# SAMC21N_Xplained_Pro_EDBG.net
KiCad netlist of a schematic drawn in Altium Designer
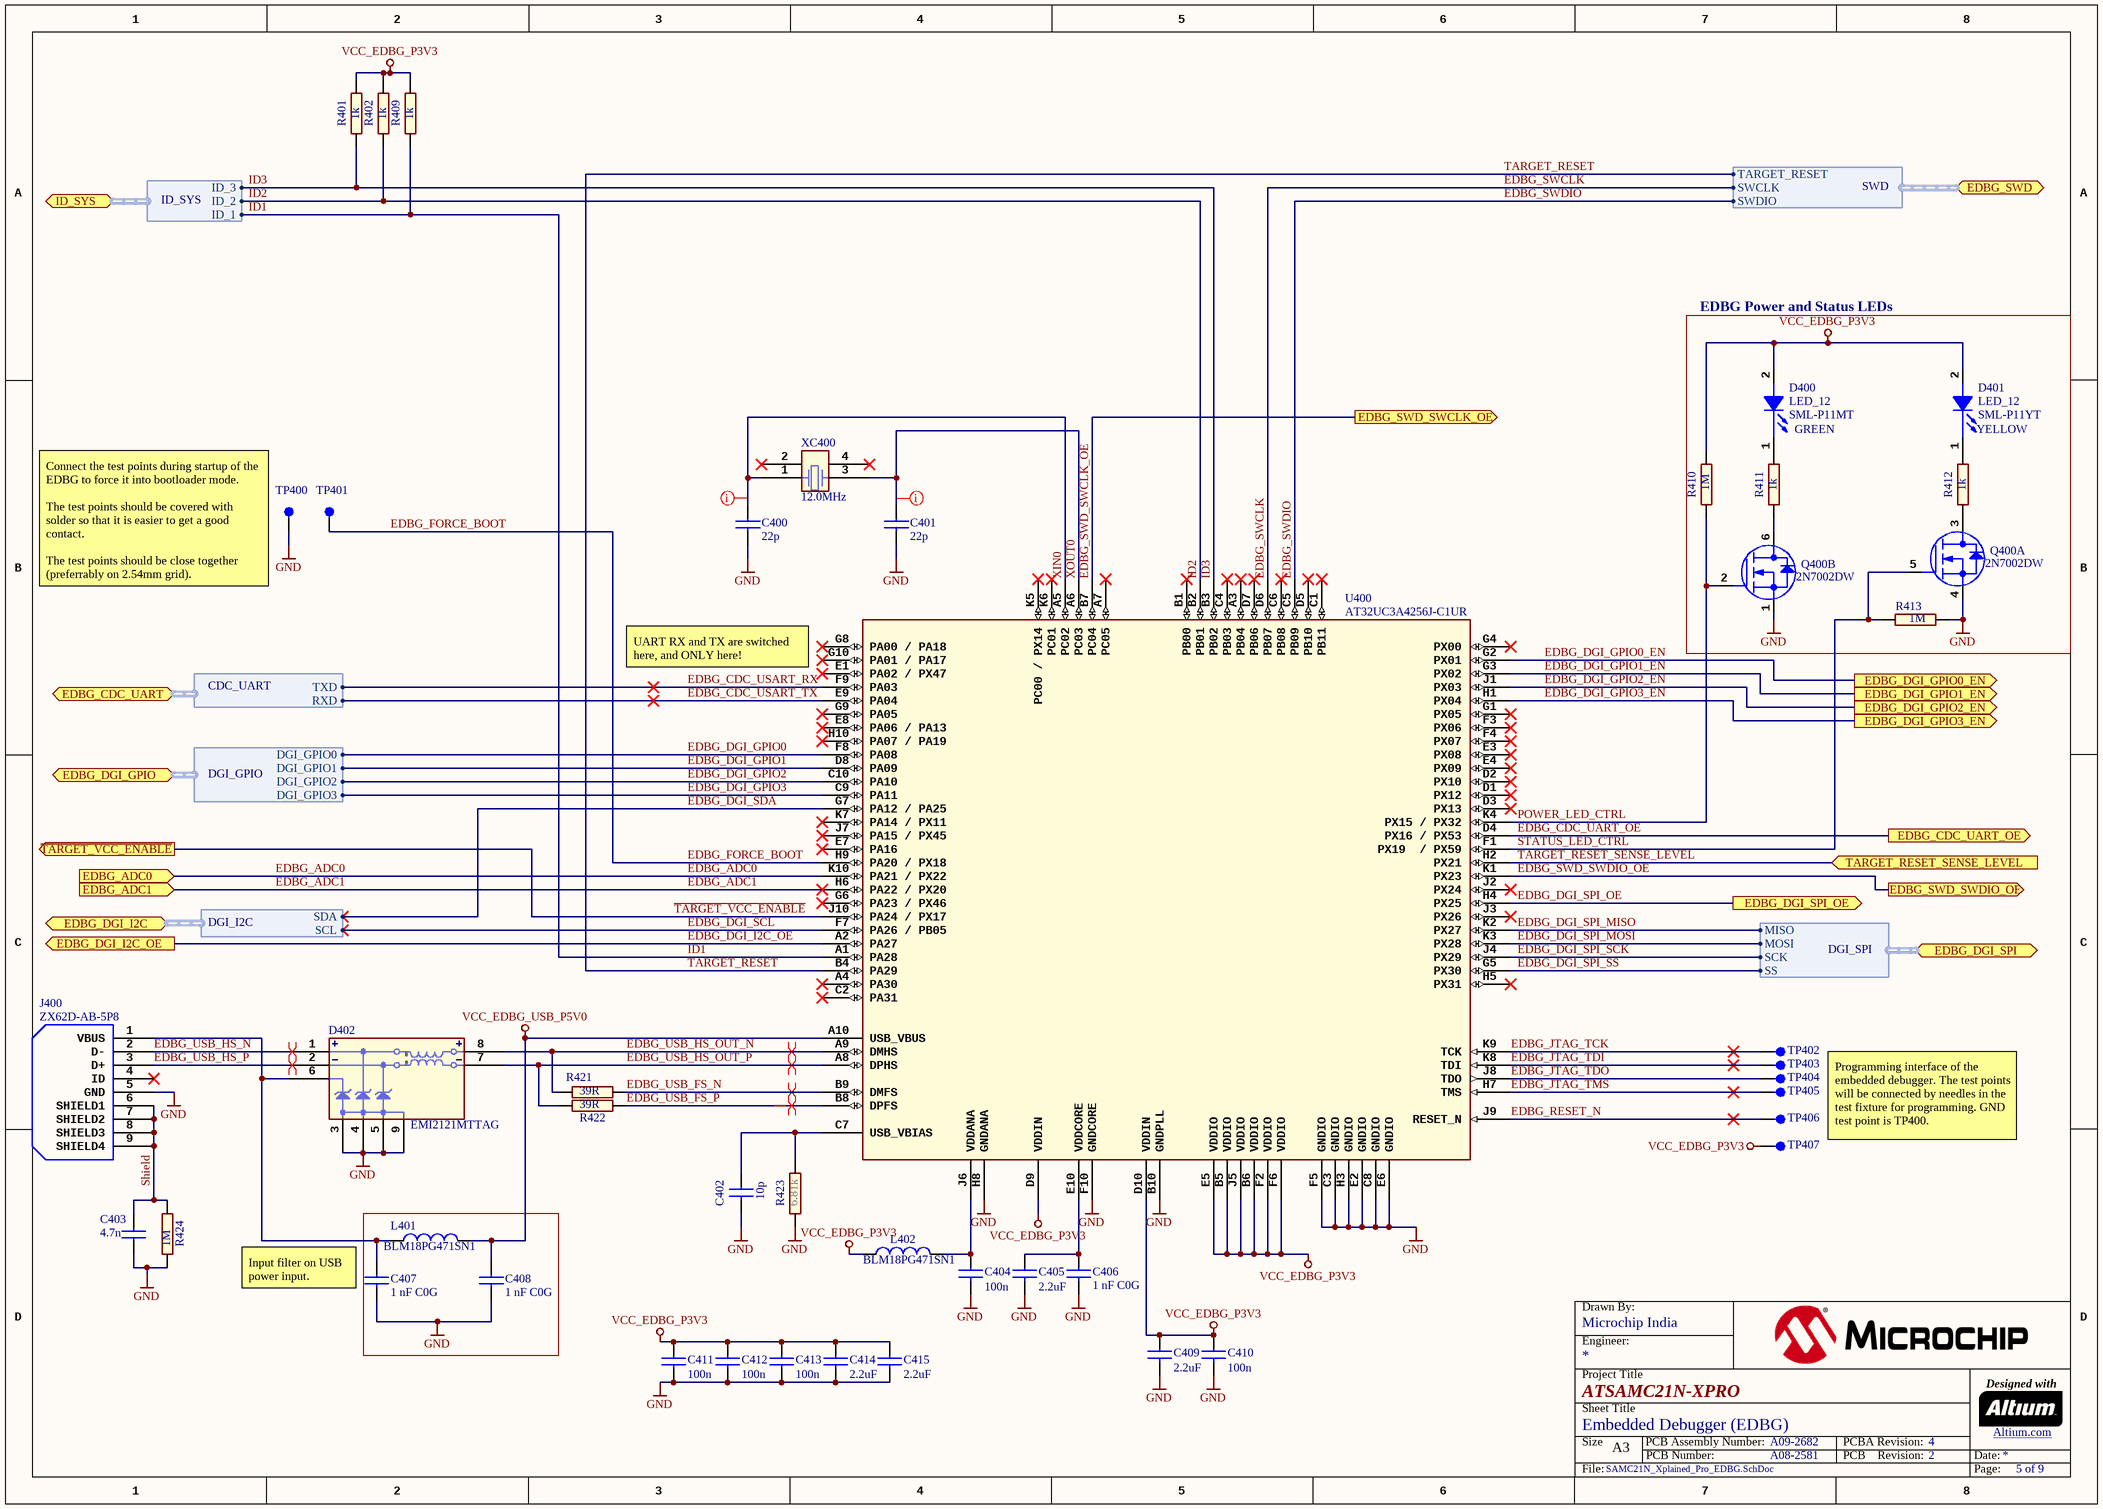
[diagram p0: SAMC21N_Xplained_Pro_EDBG.SchDoc]

(export (version "E")
  (design (tool "Eeschema 10.0.6"))
  (components
    (comp (ref "C400")
      (value "22p")
      (footprint "AP1-00053")
      (description "Ceramic capacitor, SMD 0402, NP0, 50V, +/-5%")
      (fields (field (name "TOLERANCE") "50V, +/-5%") (field (name "VERIFIED BY") "Lars Helge Mo"))
      (libsource (lib "AltiumDbLib") (part "CAP-NONPOL"))
    )
    (comp (ref "C401")
      (value "22p")
      (footprint "AP1-00053")
      (description "Ceramic capacitor, SMD 0402, NP0, 50V, +/-5%")
      (fields (field (name "TOLERANCE") "50V, +/-5%") (field (name "VERIFIED BY") "Lars Helge Mo"))
      (libsource (lib "AltiumDbLib") (part "CAP-NONPOL"))
    )
    (comp (ref "C402")
      (value "10p")
      (footprint "AP1-00053")
      (description "Ceramic capacitor, SMD 0402, NP0, 50V, +/-5%")
      (fields (field (name "TOLERANCE") "50V, +/-5%") (field (name "VERIFIED BY") "Lars Helge Mo"))
      (libsource (lib "AltiumDbLib") (part "CAP-NONPOL"))
    )
    (comp (ref "C403")
      (value "4.7n")
      (footprint "AP1-00053")
      (description "Ceramic capacitor, SMD 0402, X7R, 25V, +/-10%")
      (fields
        (field (name "TOLERANCE") "25V, +/-10%")
        (field (name "Comment") "CAP-NONPOL")
        (field (name "VERIFIED BY") "Lars Helge Mo")
      )
      (libsource (lib "AltiumDbLib") (part "CAP-NONPOL"))
    )
    (comp (ref "C404")
      (value "100n")
      (footprint "AP1-00053")
      (description "Ceramic capacitor, SMD 0402, X7R, 16V, +/-10%")
      (fields
        (field (name "TOLERANCE") "16V, +/-10%")
        (field (name "MANUFACTURER") "Kemet")
        (field (name "VERIFIED BY") "Lars Helge Mo")
      )
      (libsource (lib "AltiumDbLib") (part "CAP-NONPOL"))
    )
    (comp (ref "C405")
      (value "2.2uF")
      (footprint "AP1-00053")
      (description "Ceramic capacitor, SMD 0402, X5R, 6.3V, +/-20%")
      (fields
        (field (name "TOLERANCE") "±20%")
        (field (name "MANUFACTURER") "Kemet")
        (field (name "VERIFIED BY") "Lars Helge Mo")
      )
      (libsource (lib "AltiumDbLib") (part "CAP-NONPOL"))
    )
    (comp (ref "C406")
      (value "1 nF C0G")
      (footprint "AP1-00053")
      (description "Ceramic capacitor, SMD 0402, C0G, 50V, +/-5%")
      (fields
        (field (name "TOLERANCE") "5%")
        (field (name "MANUFACTURER") "Murata")
        (field (name "VERIFIED BY") "Lars Helge Mo")
      )
      (libsource (lib "AltiumDbLib") (part "CAP-NONPOL"))
    )
    (comp (ref "C407")
      (value "1 nF C0G")
      (footprint "AP1-00053")
      (description "Ceramic capacitor, SMD 0402, C0G, 50V, +/-5%")
      (fields
        (field (name "TOLERANCE") "5%")
        (field (name "MANUFACTURER") "Murata")
        (field (name "VERIFIED BY") "Lars Helge Mo")
      )
      (libsource (lib "AltiumDbLib") (part "CAP-NONPOL"))
    )
    (comp (ref "C408")
      (value "1 nF C0G")
      (footprint "AP1-00053")
      (description "Ceramic capacitor, SMD 0402, C0G, 50V, +/-5%")
      (fields
        (field (name "TOLERANCE") "5%")
        (field (name "MANUFACTURER") "Murata")
        (field (name "VERIFIED BY") "Lars Helge Mo")
      )
      (libsource (lib "AltiumDbLib") (part "CAP-NONPOL"))
    )
    (comp (ref "C409")
      (value "2.2uF")
      (footprint "AP1-00053")
      (description "Ceramic capacitor, SMD 0402, X5R, 6.3V, +/-20%")
      (fields
        (field (name "TOLERANCE") "±20%")
        (field (name "MANUFACTURER") "Kemet")
        (field (name "VERIFIED BY") "Lars Helge Mo")
      )
      (libsource (lib "AltiumDbLib") (part "CAP-NONPOL"))
    )
    (comp (ref "C410")
      (value "100n")
      (footprint "AP1-00053")
      (description "Ceramic capacitor, SMD 0402, X7R, 16V, +/-10%")
      (fields
        (field (name "TOLERANCE") "16V, +/-10%")
        (field (name "MANUFACTURER") "Kemet")
        (field (name "VERIFIED BY") "Lars Helge Mo")
      )
      (libsource (lib "AltiumDbLib") (part "CAP-NONPOL"))
    )
    (comp (ref "C411")
      (value "100n")
      (footprint "AP1-00053")
      (description "Ceramic capacitor, SMD 0402, X7R, 16V, +/-10%")
      (fields
        (field (name "TOLERANCE") "16V, +/-10%")
        (field (name "MANUFACTURER") "Kemet")
        (field (name "VERIFIED BY") "Lars Helge Mo")
      )
      (libsource (lib "AltiumDbLib") (part "CAP-NONPOL"))
    )
    (comp (ref "C412")
      (value "100n")
      (footprint "AP1-00053")
      (description "Ceramic capacitor, SMD 0402, X7R, 16V, +/-10%")
      (fields
        (field (name "TOLERANCE") "16V, +/-10%")
        (field (name "MANUFACTURER") "Kemet")
        (field (name "VERIFIED BY") "Lars Helge Mo")
      )
      (libsource (lib "AltiumDbLib") (part "CAP-NONPOL"))
    )
    (comp (ref "C413")
      (value "100n")
      (footprint "AP1-00053")
      (description "Ceramic capacitor, SMD 0402, X7R, 16V, +/-10%")
      (fields
        (field (name "TOLERANCE") "16V, +/-10%")
        (field (name "MANUFACTURER") "Kemet")
        (field (name "VERIFIED BY") "Lars Helge Mo")
      )
      (libsource (lib "AltiumDbLib") (part "CAP-NONPOL"))
    )
    (comp (ref "C414")
      (value "2.2uF")
      (footprint "AP1-00053")
      (description "Ceramic capacitor, SMD 0402, X5R, 6.3V, +/-20%")
      (fields
        (field (name "TOLERANCE") "±20%")
        (field (name "MANUFACTURER") "Kemet")
        (field (name "VERIFIED BY") "Lars Helge Mo")
      )
      (libsource (lib "AltiumDbLib") (part "CAP-NONPOL"))
    )
    (comp (ref "C415")
      (value "2.2uF")
      (footprint "AP1-00053")
      (description "Ceramic capacitor, SMD 0402, X5R, 6.3V, +/-20%")
      (fields
        (field (name "TOLERANCE") "±20%")
        (field (name "MANUFACTURER") "Kemet")
        (field (name "VERIFIED BY") "Lars Helge Mo")
      )
      (libsource (lib "AltiumDbLib") (part "CAP-NONPOL"))
    )
    (comp (ref "D400")
      (value "LED_12")
      (footprint "AP4-00160")
      (description "LED, SMD 0402, Green, Wave length=569nm, 2.1mcd @ (1mA, 1.9Vf)")
      (fields
        (field (name "ALTIUM_VALUE") "SML-P11MT")
        (field (name "MANUFACTURER") "ROHM")
        (field (name "MPN") "SML-P11MT-T86")
        (field (name "VERIFIED BY") "Sveinung Helgeland")
      )
      (libsource (lib "AltiumDbLib") (part "LED_12"))
    )
    (comp (ref "D401")
      (value "LED_12")
      (footprint "AP4-00160")
      (description "LED, SMD 0402, Yellow, Wave length=586nm, 7.6mcd @ (1mA, 1.9Vf)")
      (fields
        (field (name "ALTIUM_VALUE") "SML-P11YT")
        (field (name "MANUFACTURER") "ROHM")
        (field (name "MPN") "SML-P11YT-T86")
        (field (name "VERIFIED BY") "Sveinung Helgeland")
      )
      (libsource (lib "AltiumDbLib") (part "LED_12"))
    )
    (comp (ref "D402")
      (value "EMI2121MTTAG")
      (footprint "AP4-00159")
      (description "EMI2121, SZEMI2121 Single Pair Common Mode Filter with ESD Protection")
      (fields (field (name "MANUFACTURER") "ON Semiconductor") (field (name "Comment") "WDFN8"))
      (libsource (lib "AltiumDbLib") (part "EMI2121"))
    )
    (comp (ref "J400")
      (value "ZX62D-AB-5P8")
      (footprint "AP8-00852")
      (description "Micro USB AB Connector, Standard SMT + DIP")
      (fields (field (name "Comment") "2,000 pieces per reel") (field (name "VERIFIED BY") "Eirik Rasmussen"))
      (libsource (lib "AltiumDbLib") (part "USB_AB"))
    )
    (comp (ref "L401")
      (value "BLM18PG471SN1")
      (footprint "AP3-00005")
      (description "SMD RF inductor 0603. Z=470Ohm (@100MHz), Max R(dc)=0.65Ohm, Max current=1A")
      (fields
        (field (name "TOLERANCE") "±25%")
        (field (name "MANUFACTURER") "Murata")
        (field (name "VERIFIED BY") "Lars Helge Mo")
      )
      (libsource (lib "AltiumDbLib") (part "INDUCTOR"))
    )
    (comp (ref "L402")
      (value "BLM18PG471SN1")
      (footprint "AP3-00005")
      (description "SMD RF inductor 0603. Z=470Ohm (@100MHz), Max R(dc)=0.65Ohm, Max current=1A")
      (fields
        (field (name "TOLERANCE") "±25%")
        (field (name "MANUFACTURER") "Murata")
        (field (name "VERIFIED BY") "Lars Helge Mo")
      )
      (libsource (lib "AltiumDbLib") (part "INDUCTOR"))
    )
    (comp (ref "Q400")
      (value "2N7002DW")
      (footprint "AP5-00001")
      (description "Dual N-Channel MOSFET, 60V, 115mA cont,RDS(ON) < 7.5 Ohm @50mA@5V, SOT-363")
      (fields
        (field (name "MANUFACTURER") "Fairchild")
        (field (name "Comment") "Same as 2N7002 but with two MOSFETs in one package")
      )
      (libsource (lib "AltiumDbLib") (part "MOSFET_DUAL_N_S2G2D1S1G1D2"))
    )
    (comp (ref "R401")
      (value "1k")
      (footprint "AP2-00000")
      (description "Thick film resistor, SMD 0402, 1/16W, 1%")
      (fields
        (field (name "TOLERANCE") "1 %")
        (field (name "Comment") "R2")
        (field (name "VERIFIED BY") "Lars Helge Mo")
      )
      (libsource (lib "AltiumDbLib") (part "R2"))
    )
    (comp (ref "R402")
      (value "1k")
      (footprint "AP2-00000")
      (description "Thick film resistor, SMD 0402, 1/16W, 1%")
      (fields
        (field (name "TOLERANCE") "1 %")
        (field (name "Comment") "R2")
        (field (name "VERIFIED BY") "Lars Helge Mo")
      )
      (libsource (lib "AltiumDbLib") (part "R2"))
    )
    (comp (ref "R409")
      (value "1k")
      (footprint "AP2-00000")
      (description "Thick film resistor, SMD 0402, 1/16W, 1%")
      (fields
        (field (name "TOLERANCE") "1 %")
        (field (name "Comment") "R2")
        (field (name "VERIFIED BY") "Lars Helge Mo")
      )
      (libsource (lib "AltiumDbLib") (part "R2"))
    )
    (comp (ref "R410")
      (value "1M")
      (footprint "AP2-00000")
      (description "Thick film resistor, SMD 0402, 1/16W, 1%")
      (fields
        (field (name "TOLERANCE") "1 %")
        (field (name "MANUFACTURER") "KOA")
        (field (name "VERIFIED BY") "Lars Helge Mo")
      )
      (libsource (lib "AltiumDbLib") (part "R2"))
    )
    (comp (ref "R411")
      (value "1k")
      (footprint "AP2-00000")
      (description "Thick film resistor, SMD 0402, 1/16W, 1%")
      (fields
        (field (name "TOLERANCE") "1 %")
        (field (name "MANUFACTURER") "ASJ")
        (field (name "VERIFIED BY") "Lars Helge Mo")
      )
      (libsource (lib "AltiumDbLib") (part "R2"))
    )
    (comp (ref "R412")
      (value "1k")
      (footprint "AP2-00000")
      (description "Thick film resistor, SMD 0402, 1/16W, 1%")
      (fields
        (field (name "TOLERANCE") "1 %")
        (field (name "MANUFACTURER") "ASJ")
        (field (name "VERIFIED BY") "Lars Helge Mo")
      )
      (libsource (lib "AltiumDbLib") (part "R2"))
    )
    (comp (ref "R413")
      (value "1M")
      (footprint "AP2-00000")
      (description "Thick film resistor, SMD 0402, 1/16W, 1%")
      (fields
        (field (name "TOLERANCE") "1 %")
        (field (name "MANUFACTURER") "KOA")
        (field (name "VERIFIED BY") "Lars Helge Mo")
      )
      (libsource (lib "") (part "R2_2"))
    )
    (comp (ref "R421")
      (value "39R")
      (footprint "AP2-00011")
      (description "Thick film resistor, SMD 0402, 1/16W, 1%")
      (fields
        (field (name "TOLERANCE") "1 %")
        (field (name "Comment") "R2")
        (field (name "VERIFIED BY") "Lars Helge Mo")
      )
      (libsource (lib "") (part "R2_1"))
    )
    (comp (ref "R422")
      (value "39R")
      (footprint "AP2-00011")
      (description "Thick film resistor, SMD 0402, 1/16W, 1%")
      (fields
        (field (name "TOLERANCE") "1 %")
        (field (name "Comment") "R2")
        (field (name "VERIFIED BY") "Lars Helge Mo")
      )
      (libsource (lib "") (part "R2_1"))
    )
    (comp (ref "R423")
      (value "6.81k")
      (footprint "AP2-00011")
      (description "Thick film resistor, SMD 0402, 1/16W, 1%")
      (fields
        (field (name "TOLERANCE") "1%")
        (field (name "Comment") "R2")
        (field (name "VERIFIED BY") "Lars Helge Mo")
      )
      (libsource (lib "AltiumDbLib") (part "R2"))
    )
    (comp (ref "R424")
      (value "1M")
      (footprint "AP2-00011")
      (description "Thick film resistor, SMD 0402, 1/16W, 1%")
      (fields
        (field (name "TOLERANCE") "1 %")
        (field (name "MANUFACTURER") "KOA")
        (field (name "VERIFIED BY") "Lars Helge Mo")
      )
      (libsource (lib "") (part "R2_3"))
    )
    (comp (ref "TP400")
      (value "TESTPAD")
      (footprint "AP8-00010")
      (description "Single SMD testpad")
      (fields (field (name "VERIFIED BY") "Sveinung Helgeland"))
      (libsource (lib "AltiumDbLib") (part "TESTPOINT"))
    )
    (comp (ref "TP401")
      (value "TESTPAD")
      (footprint "AP8-00010")
      (description "Single SMD testpad")
      (fields (field (name "VERIFIED BY") "Sveinung Helgeland"))
      (libsource (lib "AltiumDbLib") (part "TESTPOINT"))
    )
    (comp (ref "TP402")
      (value "TESTPAD")
      (footprint "AP8-00010")
      (description "Single SMD testpad")
      (fields (field (name "VERIFIED BY") "Sveinung Helgeland"))
      (libsource (lib "AltiumDbLib") (part "TESTPOINT"))
    )
    (comp (ref "TP403")
      (value "TESTPAD")
      (footprint "AP8-00010")
      (description "Single SMD testpad")
      (fields (field (name "VERIFIED BY") "Sveinung Helgeland"))
      (libsource (lib "AltiumDbLib") (part "TESTPOINT"))
    )
    (comp (ref "TP404")
      (value "TESTPAD")
      (footprint "AP8-00010")
      (description "Single SMD testpad")
      (fields (field (name "VERIFIED BY") "Sveinung Helgeland"))
      (libsource (lib "AltiumDbLib") (part "TESTPOINT"))
    )
    (comp (ref "TP405")
      (value "TESTPAD")
      (footprint "AP8-00010")
      (description "Single SMD testpad")
      (fields (field (name "VERIFIED BY") "Sveinung Helgeland"))
      (libsource (lib "AltiumDbLib") (part "TESTPOINT"))
    )
    (comp (ref "TP406")
      (value "TESTPAD")
      (footprint "AP8-00010")
      (description "Single SMD testpad")
      (fields (field (name "VERIFIED BY") "Sveinung Helgeland"))
      (libsource (lib "AltiumDbLib") (part "TESTPOINT"))
    )
    (comp (ref "TP407")
      (value "TESTPAD")
      (footprint "AP8-00010")
      (description "Single SMD testpad")
      (fields (field (name "VERIFIED BY") "Sveinung Helgeland"))
      (libsource (lib "AltiumDbLib") (part "TESTPOINT"))
    )
    (comp (ref "U400")
      (value "AT32UC3A4256J-C1UR")
      (footprint "AP6-00206")
      (description "AVR 32-bit RISC MCU")
      (fields (field (name "MANUFACTURER") "ATMEL") (field (name "Comment") "100 ball VFBGA"))
      (libsource (lib "AltiumDbLib") (part "AT32UC3A4_VFBGA"))
    )
    (comp (ref "XC400")
      (value "12.0MHz")
      (footprint "AP7-00039")
      (description "Fox FQ5032B 12.0MHz SMD crystal 738B-12")
      (fields
        (field (name "TOLERANCE") "30PPM")
        (field (name "MANUFACTURER") "Fox  Electronics")
        (field (name "VERIFIED BY") "Ketil Skjerve")
      )
      (libsource (lib "AltiumDbLib") (part "CRYSTAL1324"))
    )
  )
  (nets
    (net (code "7") (name "/EDBG_ADC0") (class "Default")
      (node (ref "U400") (pin "K10") (pinfunction "PA21_/_PX22_K10") (pintype "bidirectional"))
    )
    (net (code "8") (name "/EDBG_ADC1") (class "Default")
      (node (ref "U400") (pin "H6") (pinfunction "PA22_/_PX20_H6") (pintype "bidirectional+no_connect"))
    )
    (net (code "9") (name "/EDBG_CDC_UART_OE") (class "Default")
      (node (ref "U400") (pin "D4") (pinfunction "PX16_/_PX53_D4") (pintype "bidirectional"))
    )
    (net (code "10") (name "/EDBG_CDC_USART_RX") (class "Default")
      (node (ref "U400") (pin "F9") (pinfunction "PA03_F9") (pintype "bidirectional"))
    )
    (net (code "11") (name "/EDBG_CDC_USART_TX") (class "Default")
      (node (ref "U400") (pin "E9") (pinfunction "PA04_E9") (pintype "bidirectional"))
    )
    (net (code "12") (name "/EDBG_DGI_GPIO0") (class "Default")
      (node (ref "U400") (pin "F8") (pinfunction "PA08_F8") (pintype "bidirectional"))
    )
    (net (code "13") (name "/EDBG_DGI_GPIO0_EN") (class "Default")
      (node (ref "U400") (pin "G2") (pinfunction "PX01_G2") (pintype "bidirectional"))
    )
    (net (code "14") (name "/EDBG_DGI_GPIO1") (class "Default")
      (node (ref "U400") (pin "D8") (pinfunction "PA09_D8") (pintype "bidirectional"))
    )
    (net (code "15") (name "/EDBG_DGI_GPIO1_EN") (class "Default")
      (node (ref "U400") (pin "G3") (pinfunction "PX02_G3") (pintype "bidirectional"))
    )
    (net (code "16") (name "/EDBG_DGI_GPIO2") (class "Default")
      (node (ref "U400") (pin "C10") (pinfunction "PA10_C10") (pintype "bidirectional"))
    )
    (net (code "17") (name "/EDBG_DGI_GPIO2_EN") (class "Default")
      (node (ref "U400") (pin "J1") (pinfunction "PX03_J1") (pintype "bidirectional"))
    )
    (net (code "18") (name "/EDBG_DGI_GPIO3") (class "Default")
      (node (ref "U400") (pin "C9") (pinfunction "PA11_C9") (pintype "bidirectional"))
    )
    (net (code "19") (name "/EDBG_DGI_GPIO3_EN") (class "Default")
      (node (ref "U400") (pin "H1") (pinfunction "PX04_H1") (pintype "bidirectional"))
    )
    (net (code "20") (name "/EDBG_DGI_I2C_OE") (class "Default")
      (node (ref "U400") (pin "A2") (pinfunction "PA27_A2") (pintype "bidirectional"))
    )
    (net (code "21") (name "/EDBG_DGI_SCL") (class "Default")
      (node (ref "U400") (pin "F7") (pinfunction "PA26_/_PB05_F7") (pintype "bidirectional+no_connect"))
    )
    (net (code "22") (name "/EDBG_DGI_SDA") (class "Default")
      (node (ref "U400") (pin "G7") (pinfunction "PA12_/_PA25_G7") (pintype "bidirectional+no_connect"))
    )
    (net (code "23") (name "/EDBG_DGI_SPI_MISO") (class "Default")
      (node (ref "U400") (pin "K2") (pinfunction "PX27_K2") (pintype "bidirectional"))
    )
    (net (code "24") (name "/EDBG_DGI_SPI_MOSI") (class "Default")
      (node (ref "U400") (pin "K3") (pinfunction "PX28_K3") (pintype "bidirectional"))
    )
    (net (code "25") (name "/EDBG_DGI_SPI_OE") (class "Default")
      (node (ref "U400") (pin "H4") (pinfunction "PX25_H4") (pintype "bidirectional"))
    )
    (net (code "26") (name "/EDBG_DGI_SPI_SCK") (class "Default")
      (node (ref "U400") (pin "J4") (pinfunction "PX29_J4") (pintype "bidirectional"))
    )
    (net (code "27") (name "/EDBG_DGI_SPI_SS") (class "Default")
      (node (ref "U400") (pin "G5") (pinfunction "PX30_G5") (pintype "bidirectional"))
    )
    (net (code "28") (name "/EDBG_FORCE_BOOT") (class "Default")
      (node (ref "TP401") (pin "1") (pinfunction "1_1") (pintype "passive"))
      (node (ref "U400") (pin "H9") (pinfunction "PA20_/_PX18_H9") (pintype "bidirectional"))
    )
    (net (code "29") (name "/EDBG_JTAG_TCK") (class "Default")
      (node (ref "TP402") (pin "1") (pinfunction "1_1") (pintype "passive"))
      (node (ref "U400") (pin "K9") (pinfunction "TCK_K9") (pintype "input"))
    )
    (net (code "30") (name "/EDBG_JTAG_TDI") (class "Default")
      (node (ref "TP403") (pin "1") (pinfunction "1_1") (pintype "passive"))
      (node (ref "U400") (pin "K8") (pinfunction "TDI_K8") (pintype "input"))
    )
    (net (code "31") (name "/EDBG_JTAG_TDO") (class "Default")
      (node (ref "TP404") (pin "1") (pinfunction "1_1") (pintype "passive"))
      (node (ref "U400") (pin "J8") (pinfunction "TDO_J8") (pintype "output"))
    )
    (net (code "32") (name "/EDBG_JTAG_TMS") (class "Default")
      (node (ref "TP405") (pin "1") (pinfunction "1_1") (pintype "passive"))
      (node (ref "U400") (pin "H7") (pinfunction "TMS_H7") (pintype "input"))
    )
    (net (code "33") (name "/EDBG_RESET_N") (class "Default")
      (node (ref "TP406") (pin "1") (pinfunction "1_1") (pintype "passive"))
      (node (ref "U400") (pin "J9") (pinfunction "RESET_N_J9") (pintype "input"))
    )
    (net (code "34") (name "/EDBG_SWCLK") (class "Default")
      (node (ref "U400") (pin "D6") (pinfunction "PB07_D6") (pintype "bidirectional"))
    )
    (net (code "35") (name "/EDBG_SWDIO") (class "Default")
      (node (ref "U400") (pin "C5") (pinfunction "PB09_C5") (pintype "bidirectional"))
    )
    (net (code "36") (name "/EDBG_SWD_SWCLK_OE") (class "Default")
      (node (ref "U400") (pin "B7") (pinfunction "PC04_B7") (pintype "bidirectional"))
    )
    (net (code "37") (name "/EDBG_SWD_SWDIO_OE") (class "Default")
      (node (ref "U400") (pin "K1") (pinfunction "PX23_K1") (pintype "bidirectional"))
    )
    (net (code "38") (name "/EDBG_USB_FS_N") (class "Default")
      (node (ref "R421") (pin "2") (pinfunction "2_2") (pintype "passive"))
      (node (ref "U400") (pin "B9") (pinfunction "DMFS_B9") (pintype "bidirectional"))
    )
    (net (code "39") (name "/EDBG_USB_FS_P") (class "Default")
      (node (ref "R422") (pin "2") (pinfunction "2_2") (pintype "passive"))
      (node (ref "U400") (pin "B8") (pinfunction "DPFS_B8") (pintype "bidirectional"))
    )
    (net (code "40") (name "/EDBG_USB_HS_N") (class "Default")
      (node (ref "D402") (pin "1") (pinfunction "DIFF1_EXT_1") (pintype "passive"))
      (node (ref "J400") (pin "2") (pinfunction "D-_2") (pintype "passive"))
    )
    (net (code "41") (name "/EDBG_USB_HS_OUT_N") (class "Default")
      (node (ref "D402") (pin "8") (pinfunction "DIFF1_INT_8") (pintype "passive"))
      (node (ref "R421") (pin "1") (pinfunction "1_1") (pintype "passive"))
      (node (ref "U400") (pin "A9") (pinfunction "DMHS_A9") (pintype "bidirectional"))
    )
    (net (code "42") (name "/EDBG_USB_HS_OUT_P") (class "Default")
      (node (ref "D402") (pin "7") (pinfunction "DIFF2_INT_7") (pintype "passive"))
      (node (ref "R422") (pin "1") (pinfunction "1_1") (pintype "passive"))
      (node (ref "U400") (pin "A8") (pinfunction "DPHS_A8") (pintype "bidirectional"))
    )
    (net (code "43") (name "/EDBG_USB_HS_P") (class "Default")
      (node (ref "D402") (pin "2") (pinfunction "DIFF2_EXT_2") (pintype "passive"))
      (node (ref "J400") (pin "3") (pinfunction "D+_3") (pintype "passive"))
    )
    (net (code "44") (name "/ID1") (class "Default")
      (node (ref "R409") (pin "1") (pinfunction "1_1") (pintype "passive"))
      (node (ref "U400") (pin "A1") (pinfunction "PA28_A1") (pintype "bidirectional"))
    )
    (net (code "45") (name "/ID2") (class "Default")
      (node (ref "R402") (pin "1") (pinfunction "1_1") (pintype "passive"))
      (node (ref "U400") (pin "B2") (pinfunction "PB01_B2") (pintype "bidirectional"))
    )
    (net (code "46") (name "/ID3") (class "Default")
      (node (ref "R401") (pin "1") (pinfunction "1_1") (pintype "passive"))
      (node (ref "U400") (pin "B3") (pinfunction "PB02_B3") (pintype "bidirectional"))
    )
    (net (code "47") (name "/POWER_LED_CTRL") (class "Default")
      (node (ref "Q400") (pin "2") (pinfunction "G2_2") (pintype "passive"))
      (node (ref "R410") (pin "1") (pinfunction "1_1") (pintype "passive"))
      (node (ref "U400") (pin "K4") (pinfunction "PX15_/_PX32_K4") (pintype "bidirectional"))
    )
    (net (code "48") (name "/STATUS_LED_CTRL") (class "Default")
      (node (ref "Q400") (pin "5") (pinfunction "G1_5") (pintype "passive"))
      (node (ref "R413") (pin "2") (pinfunction "2_2") (pintype "passive"))
      (node (ref "U400") (pin "F1") (pinfunction "PX19__/_PX59_F1") (pintype "bidirectional"))
    )
    (net (code "49") (name "/Shield") (class "Default")
      (node (ref "C403") (pin "2") (pinfunction "2_2") (pintype "passive"))
      (node (ref "J400") (pin "6") (pinfunction "SHIELD1_6") (pintype "passive"))
      (node (ref "J400") (pin "7") (pinfunction "SHIELD2_7") (pintype "passive"))
      (node (ref "J400") (pin "8") (pinfunction "SHIELD3_8") (pintype "passive"))
      (node (ref "J400") (pin "9") (pinfunction "SHIELD4_9") (pintype "passive"))
      (node (ref "R424") (pin "2") (pinfunction "2_2") (pintype "passive"))
    )
    (net (code "50") (name "/TARGET_RESET") (class "Default")
      (node (ref "U400") (pin "B4") (pinfunction "PA29_B4") (pintype "bidirectional"))
    )
    (net (code "51") (name "/TARGET_RESET_SENSE_LEVEL") (class "Default")
      (node (ref "U400") (pin "H2") (pinfunction "PX21_H2") (pintype "bidirectional"))
    )
    (net (code "52") (name "/XIN0") (class "Default")
      (node (ref "C400") (pin "1") (pinfunction "1_1") (pintype "passive"))
      (node (ref "U400") (pin "A5") (pinfunction "PC02_A5") (pintype "bidirectional"))
      (node (ref "XC400") (pin "1") (pinfunction "1_1") (pintype "passive"))
    )
    (net (code "53") (name "/XOUT0") (class "Default")
      (node (ref "C401") (pin "1") (pinfunction "1_1") (pintype "passive"))
      (node (ref "U400") (pin "A6") (pinfunction "PC03_A6") (pintype "bidirectional"))
      (node (ref "XC400") (pin "3") (pinfunction "3_3") (pintype "passive"))
    )
    (net (code "60") (name "/~{TARGET_VCC_ENABLE}") (class "Default")
      (node (ref "U400") (pin "J10") (pinfunction "PA24_/_PX17_J10") (pintype "bidirectional"))
    )
    (net (code "61") (name "GND") (class "Default")
      (node (ref "C400") (pin "2") (pinfunction "2_2") (pintype "passive"))
      (node (ref "C401") (pin "2") (pinfunction "2_2") (pintype "passive"))
      (node (ref "C402") (pin "2") (pinfunction "2_2") (pintype "passive"))
      (node (ref "C403") (pin "1") (pinfunction "1_1") (pintype "passive"))
      (node (ref "C404") (pin "2") (pinfunction "2_2") (pintype "passive"))
      (node (ref "C405") (pin "2") (pinfunction "2_2") (pintype "passive"))
      (node (ref "C406") (pin "2") (pinfunction "2_2") (pintype "passive"))
      (node (ref "C407") (pin "2") (pinfunction "2_2") (pintype "passive"))
      (node (ref "C408") (pin "2") (pinfunction "2_2") (pintype "passive"))
      (node (ref "C409") (pin "2") (pinfunction "2_2") (pintype "passive"))
      (node (ref "C410") (pin "2") (pinfunction "2_2") (pintype "passive"))
      (node (ref "C411") (pin "2") (pinfunction "2_2") (pintype "passive"))
      (node (ref "C412") (pin "2") (pinfunction "2_2") (pintype "passive"))
      (node (ref "C413") (pin "2") (pinfunction "2_2") (pintype "passive"))
      (node (ref "C414") (pin "2") (pinfunction "2_2") (pintype "passive"))
      (node (ref "C415") (pin "2") (pinfunction "2_2") (pintype "passive"))
      (node (ref "D402") (pin "3") (pinfunction "GND_3") (pintype "power_in"))
      (node (ref "D402") (pin "4") (pinfunction "GND_4") (pintype "power_in"))
      (node (ref "D402") (pin "5") (pinfunction "GND_5") (pintype "power_in"))
      (node (ref "D402") (pin "9") (pinfunction "GND_9") (pintype "power_in"))
      (node (ref "J400") (pin "5") (pinfunction "GND_5") (pintype "passive"))
      (node (ref "Q400") (pin "1") (pinfunction "S2_1") (pintype "passive"))
      (node (ref "Q400") (pin "4") (pinfunction "S1_4") (pintype "passive"))
      (node (ref "R413") (pin "1") (pinfunction "1_1") (pintype "passive"))
      (node (ref "R423") (pin "1") (pinfunction "1_1") (pintype "passive"))
      (node (ref "R424") (pin "1") (pinfunction "1_1") (pintype "passive"))
      (node (ref "TP400") (pin "1") (pinfunction "1_1") (pintype "passive"))
      (node (ref "U400") (pin "B10") (pinfunction "GNDPLL_B10") (pintype "power_in"))
      (node (ref "U400") (pin "C3") (pinfunction "GNDIO_C3") (pintype "power_in"))
      (node (ref "U400") (pin "C8") (pinfunction "GNDIO_C8") (pintype "power_in"))
      (node (ref "U400") (pin "E2") (pinfunction "GNDIO_E2") (pintype "power_in"))
      (node (ref "U400") (pin "E6") (pinfunction "GNDIO_E6") (pintype "power_in"))
      (node (ref "U400") (pin "F10") (pinfunction "GNDCORE_F10") (pintype "power_in"))
      (node (ref "U400") (pin "F5") (pinfunction "GNDIO_F5") (pintype "power_in"))
      (node (ref "U400") (pin "H3") (pinfunction "GNDIO_H3") (pintype "power_in"))
      (node (ref "U400") (pin "H8") (pinfunction "GNDANA_H8") (pintype "power_in"))
    )
    (net (code "62") (name "Net-(D400-CATHODE)") (class "Default")
      (node (ref "D400") (pin "1") (pinfunction "CATHODE_1") (pintype "passive"))
      (node (ref "R411") (pin "2") (pinfunction "2_2") (pintype "passive"))
    )
    (net (code "63") (name "Net-(D401-CATHODE)") (class "Default")
      (node (ref "D401") (pin "1") (pinfunction "CATHODE_1") (pintype "passive"))
      (node (ref "R412") (pin "2") (pinfunction "2_2") (pintype "passive"))
    )
    (net (code "64") (name "Net-(D402-VBUS)") (class "Default")
      (node (ref "C407") (pin "1") (pinfunction "1_1") (pintype "passive"))
      (node (ref "D402") (pin "6") (pinfunction "VBUS_6") (pintype "passive"))
      (node (ref "J400") (pin "1") (pinfunction "VBUS_1") (pintype "passive"))
      (node (ref "L401") (pin "1") (pinfunction "1_1") (pintype "passive"))
    )
    (net (code "65") (name "Net-(Q400A-D1)") (class "Default")
      (node (ref "Q400") (pin "3") (pinfunction "D1_3") (pintype "passive"))
      (node (ref "R412") (pin "1") (pinfunction "1_1") (pintype "passive"))
    )
    (net (code "66") (name "Net-(Q400B-D2)") (class "Default")
      (node (ref "Q400") (pin "6") (pinfunction "D2_6") (pintype "passive"))
      (node (ref "R411") (pin "1") (pinfunction "1_1") (pintype "passive"))
    )
    (net (code "67") (name "Net-(U400-USB_VBIAS)") (class "Default")
      (node (ref "C402") (pin "1") (pinfunction "1_1") (pintype "passive"))
      (node (ref "R423") (pin "2") (pinfunction "2_2") (pintype "passive"))
      (node (ref "U400") (pin "C7") (pinfunction "USB_VBIAS_C7") (pintype "power_in"))
    )
    (net (code "68") (name "Net-(U400-VDDANA)") (class "Default")
      (node (ref "C404") (pin "1") (pinfunction "1_1") (pintype "passive"))
      (node (ref "L402") (pin "2") (pinfunction "2_2") (pintype "passive"))
      (node (ref "U400") (pin "J6") (pinfunction "VDDANA_J6") (pintype "power_in"))
    )
    (net (code "69") (name "Net-(U400-VDDCORE)") (class "Default")
      (node (ref "C405") (pin "1") (pinfunction "1_1") (pintype "passive"))
      (node (ref "C406") (pin "1") (pinfunction "1_1") (pintype "passive"))
      (node (ref "U400") (pin "E10") (pinfunction "VDDCORE_E10") (pintype "power_in"))
    )
    (net (code "70") (name "VCC_EDBG_P3V3") (class "Default")
      (node (ref "C409") (pin "1") (pinfunction "1_1") (pintype "passive"))
      (node (ref "C410") (pin "1") (pinfunction "1_1") (pintype "passive"))
      (node (ref "C411") (pin "1") (pinfunction "1_1") (pintype "passive"))
      (node (ref "C412") (pin "1") (pinfunction "1_1") (pintype "passive"))
      (node (ref "C413") (pin "1") (pinfunction "1_1") (pintype "passive"))
      (node (ref "C414") (pin "1") (pinfunction "1_1") (pintype "passive"))
      (node (ref "C415") (pin "1") (pinfunction "1_1") (pintype "passive"))
      (node (ref "D400") (pin "2") (pinfunction "ANODE_2") (pintype "passive"))
      (node (ref "D401") (pin "2") (pinfunction "ANODE_2") (pintype "passive"))
      (node (ref "L402") (pin "1") (pinfunction "1_1") (pintype "passive"))
      (node (ref "R401") (pin "2") (pinfunction "2_2") (pintype "passive"))
      (node (ref "R402") (pin "2") (pinfunction "2_2") (pintype "passive"))
      (node (ref "R409") (pin "2") (pinfunction "2_2") (pintype "passive"))
      (node (ref "R410") (pin "2") (pinfunction "2_2") (pintype "passive"))
      (node (ref "TP407") (pin "1") (pinfunction "1_1") (pintype "passive"))
      (node (ref "U400") (pin "B5") (pinfunction "VDDIO_B5") (pintype "power_in"))
      (node (ref "U400") (pin "B6") (pinfunction "VDDIO_B6") (pintype "power_in"))
      (node (ref "U400") (pin "D10") (pinfunction "VDDIN_D10") (pintype "power_in"))
      (node (ref "U400") (pin "D9") (pinfunction "VDDIN_D9") (pintype "power_in"))
      (node (ref "U400") (pin "E5") (pinfunction "VDDIO_E5") (pintype "power_in"))
      (node (ref "U400") (pin "F2") (pinfunction "VDDIO_F2") (pintype "power_in"))
      (node (ref "U400") (pin "F6") (pinfunction "VDDIO_F6") (pintype "power_in"))
      (node (ref "U400") (pin "J5") (pinfunction "VDDIO_J5") (pintype "power_in"))
    )
    (net (code "71") (name "VCC_EDBG_USB_P5V0") (class "Default")
      (node (ref "C408") (pin "1") (pinfunction "1_1") (pintype "passive"))
      (node (ref "L401") (pin "2") (pinfunction "2_2") (pintype "passive"))
      (node (ref "U400") (pin "A10") (pinfunction "USB_VBUS_A10") (pintype "power_in"))
    )
    (net (code "72") (name "unconnected-(J400-ID-Pad4)") (class "Default")
      (node (ref "J400") (pin "4") (pinfunction "ID_4") (pintype "passive+no_connect"))
    )
    (net (code "73") (name "unconnected-(U400-PA00_{slash}_PA18-PadG8)") (class "Default")
      (node (ref "U400") (pin "G8") (pinfunction "PA00_/_PA18_G8") (pintype "bidirectional+no_connect"))
    )
    (net (code "74") (name "unconnected-(U400-PA01_{slash}_PA17-PadG10)") (class "Default")
      (node (ref "U400") (pin "G10") (pinfunction "PA01_/_PA17_G10") (pintype "bidirectional+no_connect"))
    )
    (net (code "75") (name "unconnected-(U400-PA02_{slash}_PX47-PadE1)") (class "Default")
      (node (ref "U400") (pin "E1") (pinfunction "PA02_/_PX47_E1") (pintype "bidirectional+no_connect"))
    )
    (net (code "76") (name "unconnected-(U400-PA05-PadG9)") (class "Default")
      (node (ref "U400") (pin "G9") (pinfunction "PA05_G9") (pintype "bidirectional+no_connect"))
    )
    (net (code "77") (name "unconnected-(U400-PA06_{slash}_PA13-PadE8)") (class "Default")
      (node (ref "U400") (pin "E8") (pinfunction "PA06_/_PA13_E8") (pintype "bidirectional+no_connect"))
    )
    (net (code "78") (name "unconnected-(U400-PA07_{slash}_PA19-PadH10)") (class "Default")
      (node (ref "U400") (pin "H10") (pinfunction "PA07_/_PA19_H10") (pintype "bidirectional+no_connect"))
    )
    (net (code "79") (name "unconnected-(U400-PA14_{slash}_PX11-PadK7)") (class "Default")
      (node (ref "U400") (pin "K7") (pinfunction "PA14_/_PX11_K7") (pintype "bidirectional+no_connect"))
    )
    (net (code "80") (name "unconnected-(U400-PA15_{slash}_PX45-PadJ7)") (class "Default")
      (node (ref "U400") (pin "J7") (pinfunction "PA15_/_PX45_J7") (pintype "bidirectional+no_connect"))
    )
    (net (code "81") (name "unconnected-(U400-PA16-PadE7)") (class "Default")
      (node (ref "U400") (pin "E7") (pinfunction "PA16_E7") (pintype "bidirectional+no_connect"))
    )
    (net (code "82") (name "unconnected-(U400-PA23_{slash}_PX46-PadG6)") (class "Default")
      (node (ref "U400") (pin "G6") (pinfunction "PA23_/_PX46_G6") (pintype "bidirectional+no_connect"))
    )
    (net (code "83") (name "unconnected-(U400-PA30-PadA4)") (class "Default")
      (node (ref "U400") (pin "A4") (pinfunction "PA30_A4") (pintype "bidirectional+no_connect"))
    )
    (net (code "84") (name "unconnected-(U400-PA31-PadC2)") (class "Default")
      (node (ref "U400") (pin "C2") (pinfunction "PA31_C2") (pintype "bidirectional+no_connect"))
    )
    (net (code "85") (name "unconnected-(U400-PB00-PadB1)") (class "Default")
      (node (ref "U400") (pin "B1") (pinfunction "PB00_B1") (pintype "bidirectional+no_connect"))
    )
    (net (code "86") (name "unconnected-(U400-PB03-PadC4)") (class "Default")
      (node (ref "U400") (pin "C4") (pinfunction "PB03_C4") (pintype "bidirectional+no_connect"))
    )
    (net (code "87") (name "unconnected-(U400-PB04-PadA3)") (class "Default")
      (node (ref "U400") (pin "A3") (pinfunction "PB04_A3") (pintype "bidirectional+no_connect"))
    )
    (net (code "88") (name "unconnected-(U400-PB06-PadD7)") (class "Default")
      (node (ref "U400") (pin "D7") (pinfunction "PB06_D7") (pintype "bidirectional+no_connect"))
    )
    (net (code "89") (name "unconnected-(U400-PB08-PadC6)") (class "Default")
      (node (ref "U400") (pin "C6") (pinfunction "PB08_C6") (pintype "bidirectional+no_connect"))
    )
    (net (code "90") (name "unconnected-(U400-PB10-PadD5)") (class "Default")
      (node (ref "U400") (pin "D5") (pinfunction "PB10_D5") (pintype "bidirectional+no_connect"))
    )
    (net (code "91") (name "unconnected-(U400-PB11-PadC1)") (class "Default")
      (node (ref "U400") (pin "C1") (pinfunction "PB11_C1") (pintype "bidirectional+no_connect"))
    )
    (net (code "92") (name "unconnected-(U400-PC00_{slash}_PX14-PadK5)") (class "Default")
      (node (ref "U400") (pin "K5") (pinfunction "PC00_/_PX14_K5") (pintype "bidirectional+no_connect"))
    )
    (net (code "93") (name "unconnected-(U400-PC01-PadK6)") (class "Default")
      (node (ref "U400") (pin "K6") (pinfunction "PC01_K6") (pintype "bidirectional+no_connect"))
    )
    (net (code "94") (name "unconnected-(U400-PC05-PadA7)") (class "Default")
      (node (ref "U400") (pin "A7") (pinfunction "PC05_A7") (pintype "bidirectional+no_connect"))
    )
    (net (code "95") (name "unconnected-(U400-PX00-PadG4)") (class "Default")
      (node (ref "U400") (pin "G4") (pinfunction "PX00_G4") (pintype "bidirectional+no_connect"))
    )
    (net (code "96") (name "unconnected-(U400-PX05-PadG1)") (class "Default")
      (node (ref "U400") (pin "G1") (pinfunction "PX05_G1") (pintype "bidirectional+no_connect"))
    )
    (net (code "97") (name "unconnected-(U400-PX06-PadF3)") (class "Default")
      (node (ref "U400") (pin "F3") (pinfunction "PX06_F3") (pintype "bidirectional+no_connect"))
    )
    (net (code "98") (name "unconnected-(U400-PX07-PadF4)") (class "Default")
      (node (ref "U400") (pin "F4") (pinfunction "PX07_F4") (pintype "bidirectional+no_connect"))
    )
    (net (code "99") (name "unconnected-(U400-PX08-PadE3)") (class "Default")
      (node (ref "U400") (pin "E3") (pinfunction "PX08_E3") (pintype "bidirectional+no_connect"))
    )
    (net (code "100") (name "unconnected-(U400-PX09-PadE4)") (class "Default")
      (node (ref "U400") (pin "E4") (pinfunction "PX09_E4") (pintype "bidirectional+no_connect"))
    )
    (net (code "101") (name "unconnected-(U400-PX10-PadD2)") (class "Default")
      (node (ref "U400") (pin "D2") (pinfunction "PX10_D2") (pintype "bidirectional+no_connect"))
    )
    (net (code "102") (name "unconnected-(U400-PX12-PadD1)") (class "Default")
      (node (ref "U400") (pin "D1") (pinfunction "PX12_D1") (pintype "bidirectional+no_connect"))
    )
    (net (code "103") (name "unconnected-(U400-PX13-PadD3)") (class "Default")
      (node (ref "U400") (pin "D3") (pinfunction "PX13_D3") (pintype "bidirectional+no_connect"))
    )
    (net (code "104") (name "unconnected-(U400-PX24-PadJ2)") (class "Default")
      (node (ref "U400") (pin "J2") (pinfunction "PX24_J2") (pintype "bidirectional+no_connect"))
    )
    (net (code "105") (name "unconnected-(U400-PX26-PadJ3)") (class "Default")
      (node (ref "U400") (pin "J3") (pinfunction "PX26_J3") (pintype "bidirectional+no_connect"))
    )
    (net (code "106") (name "unconnected-(U400-PX31-PadH5)") (class "Default")
      (node (ref "U400") (pin "H5") (pinfunction "PX31_H5") (pintype "bidirectional+no_connect"))
    )
    (net (code "107") (name "unconnected-(XC400-Pad2)") (class "Default")
      (node (ref "XC400") (pin "2") (pinfunction "2_2") (pintype "passive+no_connect"))
    )
    (net (code "108") (name "unconnected-(XC400-Pad4)") (class "Default")
      (node (ref "XC400") (pin "4") (pinfunction "4_4") (pintype "passive+no_connect"))
    )
  )
)
